# monochrome.net
KiCad netlist of a schematic drawn in EAGLE
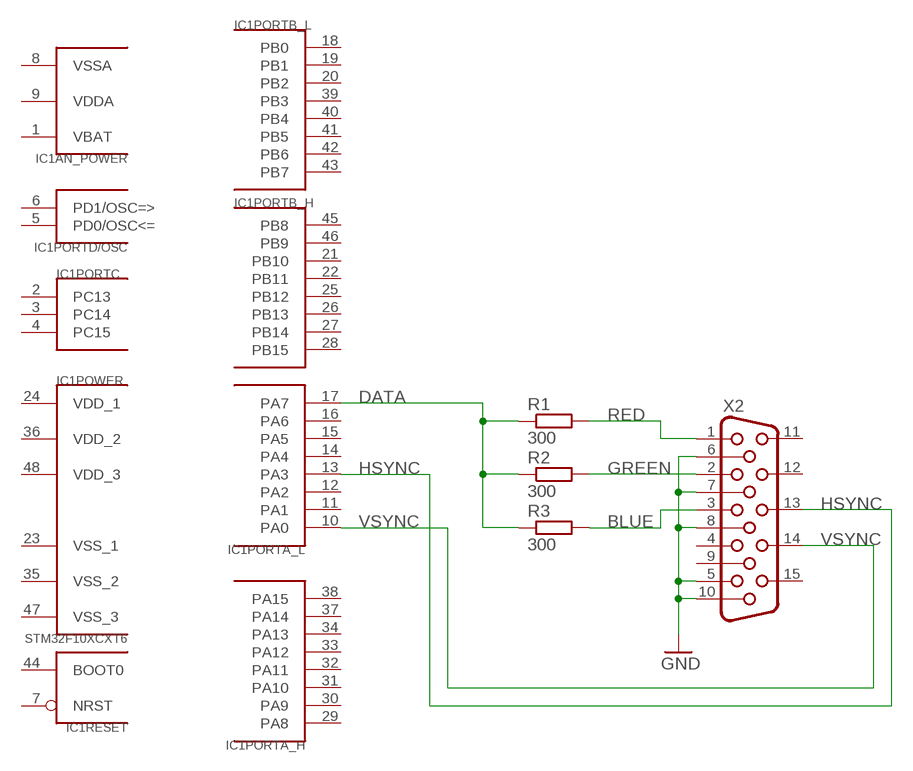
[diagram p0: schematic, sheet 1]

(export (version "E")
  (design (tool "Eeschema 10.0.6"))
  (components
    (comp (ref "IC1")
      (value "STM32F10XCXT6")
      (footprint "eagle-import:TQFP48")
      (libsource (lib "eagle-import") (part "STM32F10XCXT6"))
    )
    (comp (ref "R1")
      (value "300")
      (footprint "eagle-import:R0805")
      (libsource (lib "eagle-import") (part "R-EU_R0805"))
    )
    (comp (ref "R2")
      (value "300")
      (footprint "eagle-import:R0805")
      (libsource (lib "eagle-import") (part "R-EU_R0805"))
    )
    (comp (ref "R3")
      (value "300")
      (footprint "eagle-import:R0805")
      (libsource (lib "eagle-import") (part "R-EU_R0805"))
    )
    (comp (ref "X2")
      (value "HF15H")
      (footprint "eagle-import:HDF15H")
      (libsource (lib "eagle-import") (part "HF15H"))
    )
  )
  (nets
    (net (code "1") (name "/BLUE") (class "Default")
      (node (ref "R3") (pin "2") (pinfunction "2_2") (pintype "passive"))
      (node (ref "X2") (pin "3") (pinfunction "3_3") (pintype "passive"))
    )
    (net (code "2") (name "/DATA") (class "Default")
      (node (ref "IC1") (pin "17") (pinfunction "PA7_17") (pintype "bidirectional"))
      (node (ref "R1") (pin "1") (pinfunction "1_1") (pintype "passive"))
      (node (ref "R2") (pin "1") (pinfunction "1_1") (pintype "passive"))
      (node (ref "R3") (pin "1") (pinfunction "1_1") (pintype "passive"))
    )
    (net (code "3") (name "/GREEN") (class "Default")
      (node (ref "R2") (pin "2") (pinfunction "2_2") (pintype "passive"))
      (node (ref "X2") (pin "2") (pinfunction "2_2") (pintype "passive"))
    )
    (net (code "4") (name "/HSYNC") (class "Default")
      (node (ref "IC1") (pin "13") (pinfunction "PA3_13") (pintype "bidirectional"))
      (node (ref "X2") (pin "13") (pinfunction "13_13") (pintype "passive"))
    )
    (net (code "5") (name "/RED") (class "Default")
      (node (ref "R1") (pin "2") (pinfunction "2_2") (pintype "passive"))
      (node (ref "X2") (pin "1") (pinfunction "1_1") (pintype "passive"))
    )
    (net (code "6") (name "/VBAT") (class "Default")
      (node (ref "IC1") (pin "1") (pinfunction "VBAT_1") (pintype "power_in"))
    )
    (net (code "7") (name "/VDDA") (class "Default")
      (node (ref "IC1") (pin "9") (pinfunction "VDDA_9") (pintype "power_in"))
    )
    (net (code "8") (name "/VDD_1") (class "Default")
      (node (ref "IC1") (pin "24") (pinfunction "VDD_1_24") (pintype "power_in"))
    )
    (net (code "9") (name "/VDD_2") (class "Default")
      (node (ref "IC1") (pin "36") (pinfunction "VDD_2_36") (pintype "power_in"))
    )
    (net (code "10") (name "/VDD_3") (class "Default")
      (node (ref "IC1") (pin "48") (pinfunction "VDD_3_48") (pintype "power_in"))
    )
    (net (code "11") (name "/VSSA") (class "Default")
      (node (ref "IC1") (pin "8") (pinfunction "VSSA_8") (pintype "power_in"))
    )
    (net (code "12") (name "/VSS_1") (class "Default")
      (node (ref "IC1") (pin "23") (pinfunction "VSS_1_23") (pintype "power_in"))
    )
    (net (code "13") (name "/VSS_2") (class "Default")
      (node (ref "IC1") (pin "35") (pinfunction "VSS_2_35") (pintype "power_in"))
    )
    (net (code "14") (name "/VSS_3") (class "Default")
      (node (ref "IC1") (pin "47") (pinfunction "VSS_3_47") (pintype "power_in"))
    )
    (net (code "15") (name "/VSYNC") (class "Default")
      (node (ref "IC1") (pin "10") (pinfunction "PA0_10") (pintype "bidirectional"))
      (node (ref "X2") (pin "14") (pinfunction "14_14") (pintype "passive"))
    )
    (net (code "16") (name "GND") (class "Default")
      (node (ref "X2") (pin "10") (pinfunction "10_10") (pintype "passive"))
      (node (ref "X2") (pin "5") (pinfunction "5_5") (pintype "passive"))
      (node (ref "X2") (pin "6") (pinfunction "6_6") (pintype "passive"))
      (node (ref "X2") (pin "7") (pinfunction "7_7") (pintype "passive"))
      (node (ref "X2") (pin "8") (pinfunction "8_8") (pintype "passive"))
    )
    (net (code "17") (name "unconnected-(IC1B-PA8-Pad29)") (class "Default")
      (node (ref "IC1") (pin "29") (pinfunction "PA8_29") (pintype "bidirectional"))
    )
    (net (code "18") (name "unconnected-(IC1B-PA9-Pad30)") (class "Default")
      (node (ref "IC1") (pin "30") (pinfunction "PA9_30") (pintype "bidirectional"))
    )
    (net (code "19") (name "unconnected-(IC1B-PA10-Pad31)") (class "Default")
      (node (ref "IC1") (pin "31") (pinfunction "PA10_31") (pintype "bidirectional"))
    )
    (net (code "20") (name "unconnected-(IC1B-PA11-Pad32)") (class "Default")
      (node (ref "IC1") (pin "32") (pinfunction "PA11_32") (pintype "bidirectional"))
    )
    (net (code "21") (name "unconnected-(IC1B-PA12-Pad33)") (class "Default")
      (node (ref "IC1") (pin "33") (pinfunction "PA12_33") (pintype "bidirectional"))
    )
    (net (code "22") (name "unconnected-(IC1B-PA13-Pad34)") (class "Default")
      (node (ref "IC1") (pin "34") (pinfunction "PA13_34") (pintype "bidirectional"))
    )
    (net (code "23") (name "unconnected-(IC1B-PA14-Pad37)") (class "Default")
      (node (ref "IC1") (pin "37") (pinfunction "PA14_37") (pintype "bidirectional"))
    )
    (net (code "24") (name "unconnected-(IC1B-PA15-Pad38)") (class "Default")
      (node (ref "IC1") (pin "38") (pinfunction "PA15_38") (pintype "bidirectional"))
    )
    (net (code "25") (name "unconnected-(IC1C-PA1-Pad11)") (class "Default")
      (node (ref "IC1") (pin "11") (pinfunction "PA1_11") (pintype "bidirectional"))
    )
    (net (code "26") (name "unconnected-(IC1C-PA2-Pad12)") (class "Default")
      (node (ref "IC1") (pin "12") (pinfunction "PA2_12") (pintype "bidirectional"))
    )
    (net (code "27") (name "unconnected-(IC1C-PA4-Pad14)") (class "Default")
      (node (ref "IC1") (pin "14") (pinfunction "PA4_14") (pintype "bidirectional"))
    )
    (net (code "28") (name "unconnected-(IC1C-PA5-Pad15)") (class "Default")
      (node (ref "IC1") (pin "15") (pinfunction "PA5_15") (pintype "bidirectional"))
    )
    (net (code "29") (name "unconnected-(IC1C-PA6-Pad16)") (class "Default")
      (node (ref "IC1") (pin "16") (pinfunction "PA6_16") (pintype "bidirectional"))
    )
    (net (code "30") (name "unconnected-(IC1D-PB8-Pad45)") (class "Default")
      (node (ref "IC1") (pin "45") (pinfunction "PB8_45") (pintype "bidirectional"))
    )
    (net (code "31") (name "unconnected-(IC1D-PB9-Pad46)") (class "Default")
      (node (ref "IC1") (pin "46") (pinfunction "PB9_46") (pintype "bidirectional"))
    )
    (net (code "32") (name "unconnected-(IC1D-PB10-Pad21)") (class "Default")
      (node (ref "IC1") (pin "21") (pinfunction "PB10_21") (pintype "bidirectional"))
    )
    (net (code "33") (name "unconnected-(IC1D-PB11-Pad22)") (class "Default")
      (node (ref "IC1") (pin "22") (pinfunction "PB11_22") (pintype "bidirectional"))
    )
    (net (code "34") (name "unconnected-(IC1D-PB12-Pad25)") (class "Default")
      (node (ref "IC1") (pin "25") (pinfunction "PB12_25") (pintype "bidirectional"))
    )
    (net (code "35") (name "unconnected-(IC1D-PB13-Pad26)") (class "Default")
      (node (ref "IC1") (pin "26") (pinfunction "PB13_26") (pintype "bidirectional"))
    )
    (net (code "36") (name "unconnected-(IC1D-PB14-Pad27)") (class "Default")
      (node (ref "IC1") (pin "27") (pinfunction "PB14_27") (pintype "bidirectional"))
    )
    (net (code "37") (name "unconnected-(IC1D-PB15-Pad28)") (class "Default")
      (node (ref "IC1") (pin "28") (pinfunction "PB15_28") (pintype "bidirectional"))
    )
    (net (code "38") (name "unconnected-(IC1E-PB0-Pad18)") (class "Default")
      (node (ref "IC1") (pin "18") (pinfunction "PB0_18") (pintype "bidirectional"))
    )
    (net (code "39") (name "unconnected-(IC1E-PB1-Pad19)") (class "Default")
      (node (ref "IC1") (pin "19") (pinfunction "PB1_19") (pintype "bidirectional"))
    )
    (net (code "40") (name "unconnected-(IC1E-PB2-Pad20)") (class "Default")
      (node (ref "IC1") (pin "20") (pinfunction "PB2_20") (pintype "bidirectional"))
    )
    (net (code "41") (name "unconnected-(IC1E-PB3-Pad39)") (class "Default")
      (node (ref "IC1") (pin "39") (pinfunction "PB3_39") (pintype "bidirectional"))
    )
    (net (code "42") (name "unconnected-(IC1E-PB4-Pad40)") (class "Default")
      (node (ref "IC1") (pin "40") (pinfunction "PB4_40") (pintype "bidirectional"))
    )
    (net (code "43") (name "unconnected-(IC1E-PB5-Pad41)") (class "Default")
      (node (ref "IC1") (pin "41") (pinfunction "PB5_41") (pintype "bidirectional"))
    )
    (net (code "44") (name "unconnected-(IC1E-PB6-Pad42)") (class "Default")
      (node (ref "IC1") (pin "42") (pinfunction "PB6_42") (pintype "bidirectional"))
    )
    (net (code "45") (name "unconnected-(IC1E-PB7-Pad43)") (class "Default")
      (node (ref "IC1") (pin "43") (pinfunction "PB7_43") (pintype "bidirectional"))
    )
    (net (code "46") (name "unconnected-(IC1F-PC13-Pad2)") (class "Default")
      (node (ref "IC1") (pin "2") (pinfunction "PC13_2") (pintype "bidirectional"))
    )
    (net (code "47") (name "unconnected-(IC1F-PC14-Pad3)") (class "Default")
      (node (ref "IC1") (pin "3") (pinfunction "PC14_3") (pintype "bidirectional"))
    )
    (net (code "48") (name "unconnected-(IC1F-PC15-Pad4)") (class "Default")
      (node (ref "IC1") (pin "4") (pinfunction "PC15_4") (pintype "bidirectional"))
    )
    (net (code "49") (name "unconnected-(IC1G-PD0{slash}OSC<=-Pad5)") (class "Default")
      (node (ref "IC1") (pin "5") (pinfunction "PD0/OSC<=_5") (pintype "bidirectional"))
    )
    (net (code "50") (name "unconnected-(IC1G-PD1{slash}OSC=>-Pad6)") (class "Default")
      (node (ref "IC1") (pin "6") (pinfunction "PD1/OSC=>_6") (pintype "bidirectional"))
    )
    (net (code "51") (name "unconnected-(IC1I-BOOT0-Pad44)") (class "Default")
      (node (ref "IC1") (pin "44") (pinfunction "BOOT0_44") (pintype "input"))
    )
    (net (code "52") (name "unconnected-(IC1I-NRST-Pad7)") (class "Default")
      (node (ref "IC1") (pin "7") (pinfunction "NRST_7") (pintype "input"))
    )
    (net (code "53") (name "unconnected-(X2-Pad4)") (class "Default")
      (node (ref "X2") (pin "4") (pinfunction "4_4") (pintype "passive"))
    )
    (net (code "54") (name "unconnected-(X2-Pad9)") (class "Default")
      (node (ref "X2") (pin "9") (pinfunction "9_9") (pintype "passive"))
    )
    (net (code "55") (name "unconnected-(X2-Pad11)") (class "Default")
      (node (ref "X2") (pin "11") (pinfunction "11_11") (pintype "passive"))
    )
    (net (code "56") (name "unconnected-(X2-Pad12)") (class "Default")
      (node (ref "X2") (pin "12") (pinfunction "12_12") (pintype "passive"))
    )
    (net (code "57") (name "unconnected-(X2-Pad15)") (class "Default")
      (node (ref "X2") (pin "15") (pinfunction "15_15") (pintype "passive"))
    )
  )
)
